# teensyPCB.net
KiCad netlist of a schematic drawn in EAGLE
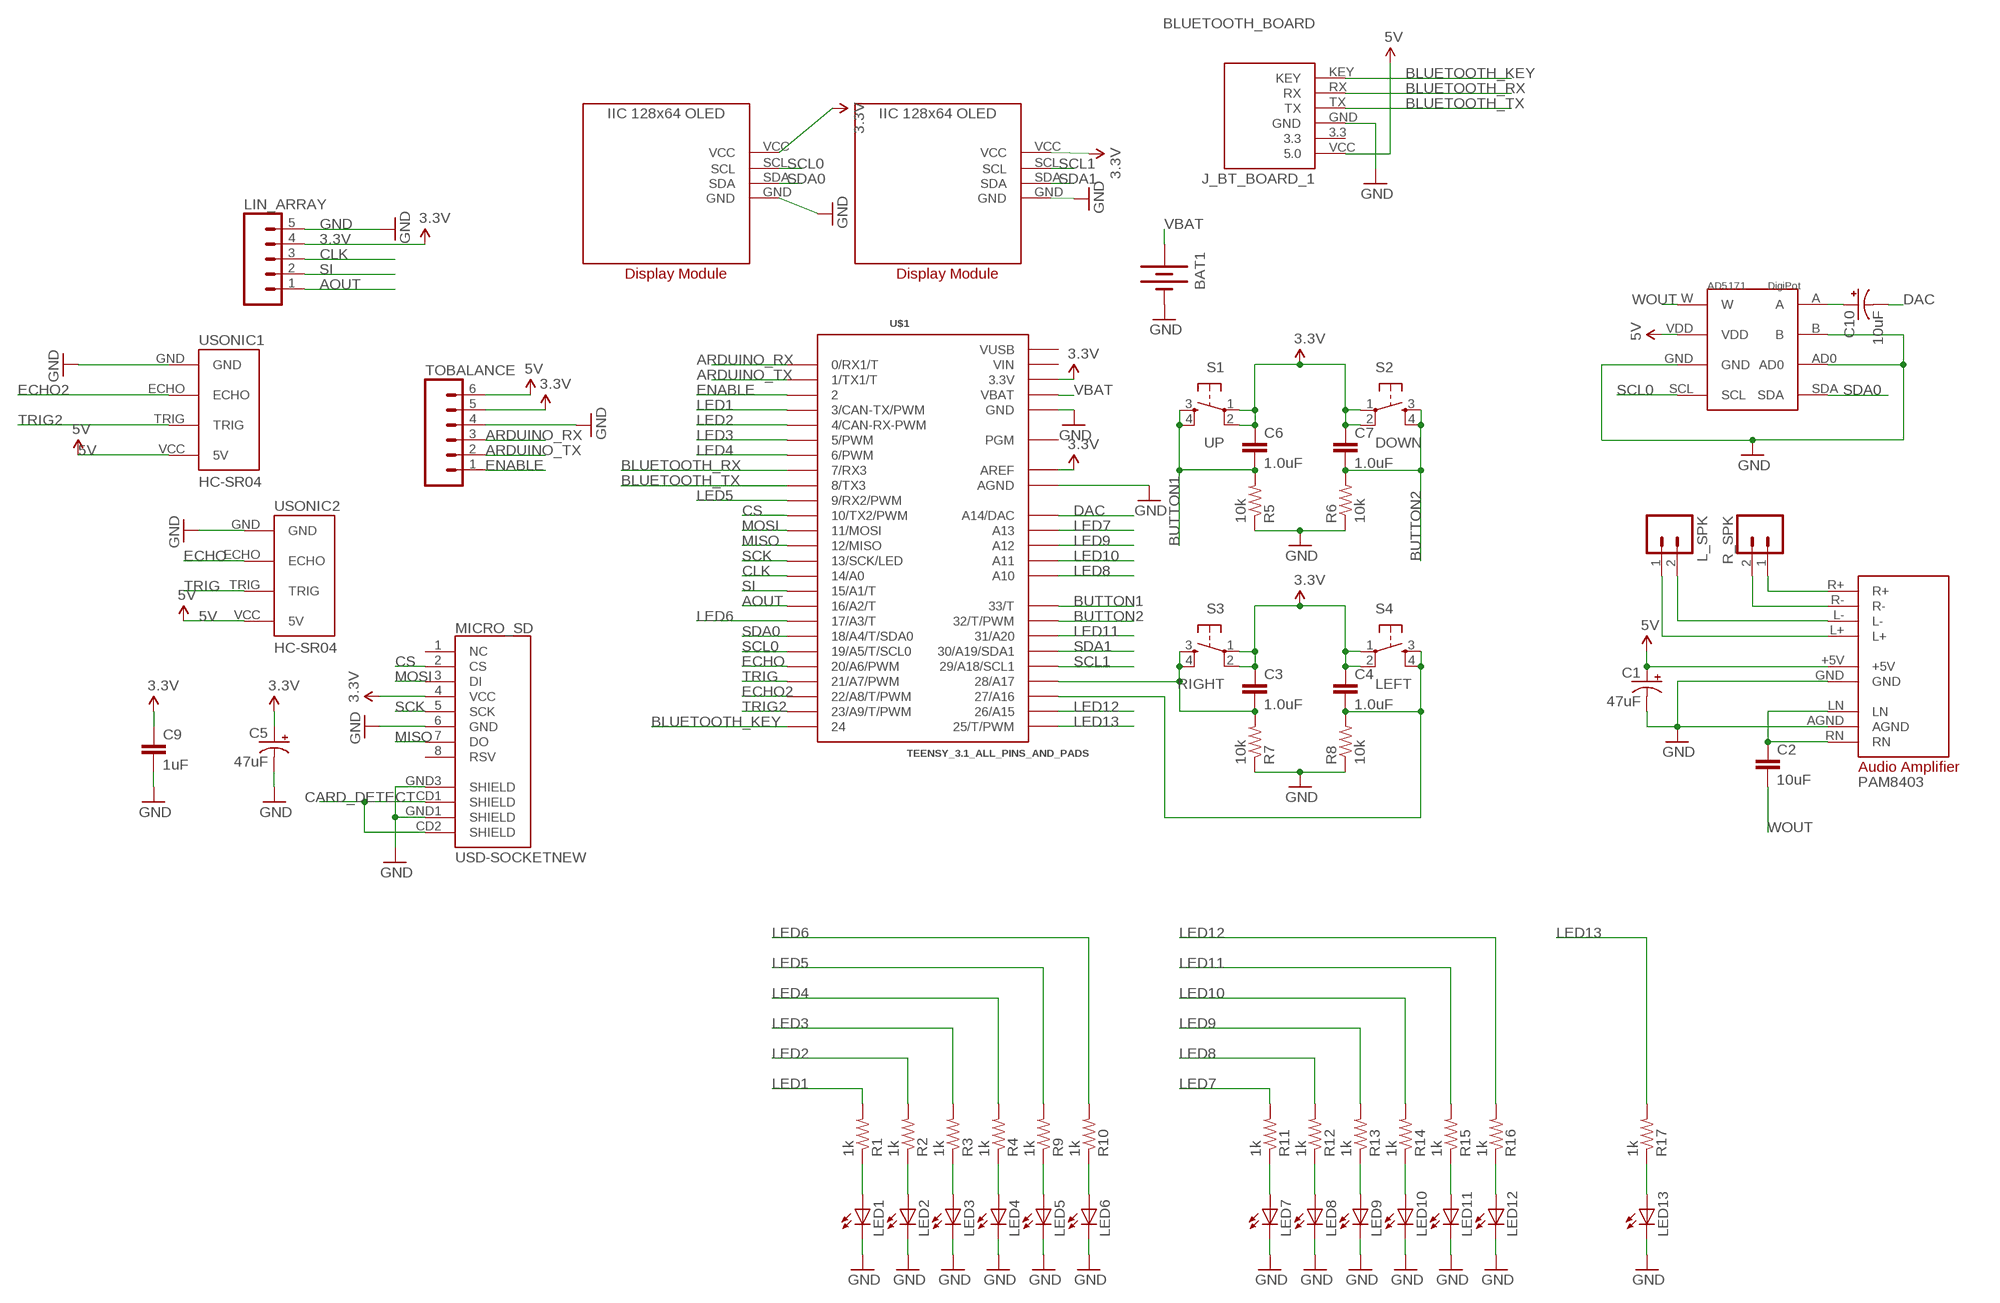
[diagram p0: schematic, sheet 1]

(export (version "E")
  (design (tool "Eeschema 10.0.6"))
  (components
    (comp (ref "BAT1")
      (value "BATTERY20PTH")
      (footprint "eagle-import:BATTCOM_20MM_PTH")
      (libsource (lib "eagle-import") (part "BATTERY20PTH"))
    )
    (comp (ref "C1")
      (value "47uF")
      (footprint "eagle-import:EIA3528")
      (libsource (lib "eagle-import") (part "CAP_POL3528"))
    )
    (comp (ref "C2")
      (value "10uF")
      (footprint "eagle-import:0805")
      (libsource (lib "eagle-import") (part "1.0UF-25V-+80/-20(0805)"))
    )
    (comp (ref "C3")
      (value "1.0uF")
      (footprint "eagle-import:0805")
      (libsource (lib "eagle-import") (part "1.0UF-25V-+80/-20(0805)"))
    )
    (comp (ref "C4")
      (value "1.0uF")
      (footprint "eagle-import:0805")
      (libsource (lib "eagle-import") (part "1.0UF-25V-+80/-20(0805)"))
    )
    (comp (ref "C5")
      (value "47uF")
      (footprint "eagle-import:EIA3528")
      (libsource (lib "eagle-import") (part "CAP_POL3528"))
    )
    (comp (ref "C6")
      (value "1.0uF")
      (footprint "eagle-import:0805")
      (libsource (lib "eagle-import") (part "1.0UF-25V-+80/-20(0805)"))
    )
    (comp (ref "C7")
      (value "1.0uF")
      (footprint "eagle-import:0805")
      (libsource (lib "eagle-import") (part "1.0UF-25V-+80/-20(0805)"))
    )
    (comp (ref "C9")
      (value "1uF")
      (footprint "eagle-import:0805")
      (libsource (lib "eagle-import") (part "1.0UF-25V-+80/-20(0805)"))
    )
    (comp (ref "C10")
      (value "10uF")
      (footprint "eagle-import:EIA3528")
      (libsource (lib "eagle-import") (part "CAP_POL3528"))
    )
    (comp (ref "J_BT_BOARD_1")
      (value "BLUETOOTH_BOARD")
      (footprint "eagle-import:BT_BOARD_FOOTPRINT")
      (libsource (lib "eagle-import") (part "BLUETOOTH_BOARD"))
    )
    (comp (ref "LED1")
      (value "LEDCHIP-LED0805")
      (footprint "eagle-import:CHIP-LED0805")
      (libsource (lib "eagle-import") (part "LEDCHIP-LED0805"))
    )
    (comp (ref "LED2")
      (value "LEDCHIP-LED0805")
      (footprint "eagle-import:CHIP-LED0805")
      (libsource (lib "eagle-import") (part "LEDCHIP-LED0805"))
    )
    (comp (ref "LED3")
      (value "LEDCHIP-LED0805")
      (footprint "eagle-import:CHIP-LED0805")
      (libsource (lib "eagle-import") (part "LEDCHIP-LED0805"))
    )
    (comp (ref "LED4")
      (value "LEDCHIP-LED0805")
      (footprint "eagle-import:CHIP-LED0805")
      (libsource (lib "eagle-import") (part "LEDCHIP-LED0805"))
    )
    (comp (ref "LED5")
      (value "LEDCHIP-LED0805")
      (footprint "eagle-import:CHIP-LED0805")
      (libsource (lib "eagle-import") (part "LEDCHIP-LED0805"))
    )
    (comp (ref "LED6")
      (value "LEDCHIP-LED0805")
      (footprint "eagle-import:CHIP-LED0805")
      (libsource (lib "eagle-import") (part "LEDCHIP-LED0805"))
    )
    (comp (ref "LED7")
      (value "LEDCHIP-LED0805")
      (footprint "eagle-import:CHIP-LED0805")
      (libsource (lib "eagle-import") (part "LEDCHIP-LED0805"))
    )
    (comp (ref "LED8")
      (value "LEDCHIP-LED0805")
      (footprint "eagle-import:CHIP-LED0805")
      (libsource (lib "eagle-import") (part "LEDCHIP-LED0805"))
    )
    (comp (ref "LED9")
      (value "LEDCHIP-LED0805")
      (footprint "eagle-import:CHIP-LED0805")
      (libsource (lib "eagle-import") (part "LEDCHIP-LED0805"))
    )
    (comp (ref "LED10")
      (value "LEDCHIP-LED0805")
      (footprint "eagle-import:CHIP-LED0805")
      (libsource (lib "eagle-import") (part "LEDCHIP-LED0805"))
    )
    (comp (ref "LED11")
      (value "LEDCHIP-LED0805")
      (footprint "eagle-import:CHIP-LED0805")
      (libsource (lib "eagle-import") (part "LEDCHIP-LED0805"))
    )
    (comp (ref "LED12")
      (value "LEDCHIP-LED0805")
      (footprint "eagle-import:CHIP-LED0805")
      (libsource (lib "eagle-import") (part "LEDCHIP-LED0805"))
    )
    (comp (ref "LED13")
      (value "LEDCHIP-LED0805")
      (footprint "eagle-import:CHIP-LED0805")
      (libsource (lib "eagle-import") (part "LEDCHIP-LED0805"))
    )
    (comp (ref "LIN_ARRAY")
      (value "M05LOCK")
      (footprint "eagle-import:1X05_LOCK")
      (libsource (lib "eagle-import") (part "M05LOCK"))
    )
    (comp (ref "L_SPK")
      (value "M02PTH")
      (footprint "eagle-import:1X02")
      (libsource (lib "eagle-import") (part "M02PTH"))
    )
    (comp (ref "MICRO_SD")
      (value "USD-SOCKETNEW")
      (footprint "eagle-import:MICRO-SD-SOCKET-PP")
      (libsource (lib "eagle-import") (part "USD-SOCKETNEW"))
    )
    (comp (ref "R1")
      (value "1k")
      (footprint "eagle-import:0805")
      (libsource (lib "eagle-import") (part "RESISTOR0805-RES"))
    )
    (comp (ref "R2")
      (value "1k")
      (footprint "eagle-import:0805")
      (libsource (lib "eagle-import") (part "RESISTOR0805-RES"))
    )
    (comp (ref "R3")
      (value "1k")
      (footprint "eagle-import:0805")
      (libsource (lib "eagle-import") (part "RESISTOR0805-RES"))
    )
    (comp (ref "R4")
      (value "1k")
      (footprint "eagle-import:0805")
      (libsource (lib "eagle-import") (part "RESISTOR0805-RES"))
    )
    (comp (ref "R5")
      (value "10k")
      (footprint "eagle-import:0805")
      (libsource (lib "eagle-import") (part "RESISTOR0805-RES"))
    )
    (comp (ref "R6")
      (value "10k")
      (footprint "eagle-import:0805")
      (libsource (lib "eagle-import") (part "RESISTOR0805-RES"))
    )
    (comp (ref "R7")
      (value "10k")
      (footprint "eagle-import:0805")
      (libsource (lib "eagle-import") (part "RESISTOR0805-RES"))
    )
    (comp (ref "R8")
      (value "10k")
      (footprint "eagle-import:0805")
      (libsource (lib "eagle-import") (part "RESISTOR0805-RES"))
    )
    (comp (ref "R9")
      (value "1k")
      (footprint "eagle-import:0805")
      (libsource (lib "eagle-import") (part "RESISTOR0805-RES"))
    )
    (comp (ref "R10")
      (value "1k")
      (footprint "eagle-import:0805")
      (libsource (lib "eagle-import") (part "RESISTOR0805-RES"))
    )
    (comp (ref "R11")
      (value "1k")
      (footprint "eagle-import:0805")
      (libsource (lib "eagle-import") (part "RESISTOR0805-RES"))
    )
    (comp (ref "R12")
      (value "1k")
      (footprint "eagle-import:0805")
      (libsource (lib "eagle-import") (part "RESISTOR0805-RES"))
    )
    (comp (ref "R13")
      (value "1k")
      (footprint "eagle-import:0805")
      (libsource (lib "eagle-import") (part "RESISTOR0805-RES"))
    )
    (comp (ref "R14")
      (value "1k")
      (footprint "eagle-import:0805")
      (libsource (lib "eagle-import") (part "RESISTOR0805-RES"))
    )
    (comp (ref "R15")
      (value "1k")
      (footprint "eagle-import:0805")
      (libsource (lib "eagle-import") (part "RESISTOR0805-RES"))
    )
    (comp (ref "R16")
      (value "1k")
      (footprint "eagle-import:0805")
      (libsource (lib "eagle-import") (part "RESISTOR0805-RES"))
    )
    (comp (ref "R17")
      (value "1k")
      (footprint "eagle-import:0805")
      (libsource (lib "eagle-import") (part "RESISTOR0805-RES"))
    )
    (comp (ref "R_SPK")
      (value "M02PTH")
      (footprint "eagle-import:1X02")
      (libsource (lib "eagle-import") (part "M02PTH"))
    )
    (comp (ref "S1")
      (value "UP")
      (footprint "eagle-import:TACTILE-SWITCH-SMD")
      (libsource (lib "eagle-import") (part "TAC_SWITCHSMD"))
    )
    (comp (ref "S2")
      (value "DOWN")
      (footprint "eagle-import:TACTILE-SWITCH-SMD")
      (libsource (lib "eagle-import") (part "TAC_SWITCHSMD"))
    )
    (comp (ref "S3")
      (value "RIGHT")
      (footprint "eagle-import:TACTILE-SWITCH-SMD")
      (libsource (lib "eagle-import") (part "TAC_SWITCHSMD"))
    )
    (comp (ref "S4")
      (value "LEFT")
      (footprint "eagle-import:TACTILE-SWITCH-SMD")
      (libsource (lib "eagle-import") (part "TAC_SWITCHSMD"))
    )
    (comp (ref "TOBALANCE")
      (value "M06POLAR_LOCK")
      (footprint "eagle-import:MOLEX-1X6_LOCK")
      (libsource (lib "eagle-import") (part "M06POLAR_LOCK"))
    )
    (comp (ref "U$1")
      (value "TEENSY_3.1_ALL_PINS_AND_PADS")
      (footprint "eagle-import:TEENSY3_ALL_PINS_&_PADS")
      (libsource (lib "eagle-import") (part "TEENSY_3.1_ALL_PINS_AND_PADS"))
    )
    (comp (ref "U$2")
      (value "IIC128X64OLED")
      (footprint "eagle-import:IIC128X64OLED")
      (libsource (lib "eagle-import") (part "IIC128X64OLED"))
    )
    (comp (ref "U$3")
      (value "IIC128X64OLED")
      (footprint "eagle-import:IIC128X64OLED")
      (libsource (lib "eagle-import") (part "IIC128X64OLED"))
    )
    (comp (ref "U$4")
      (value "AUDIOAMPEBAY_VERSION")
      (footprint "eagle-import:AUDIOAMP")
      (libsource (lib "eagle-import") (part "AUDIOAMPEBAY_VERSION"))
    )
    (comp (ref "U$5")
      (value "DIGIPOT")
      (footprint "eagle-import:SOT23-8L")
      (libsource (lib "eagle-import") (part "DIGIPOT"))
    )
    (comp (ref "USONIC1")
      (value "HC-SR04")
      (footprint "eagle-import:HC-SR04_FOOTPRINT")
      (libsource (lib "eagle-import") (part "HC-SR04"))
    )
    (comp (ref "USONIC2")
      (value "HC-SR04")
      (footprint "eagle-import:HC-SR04_FOOTPRINT")
      (libsource (lib "eagle-import") (part "HC-SR04"))
    )
  )
  (nets
    (net (code "1") (name "/AOUT") (class "Default")
      (node (ref "LIN_ARRAY") (pin "1") (pinfunction "1_1") (pintype "passive"))
      (node (ref "U$1") (pin "16/A2") (pinfunction "16/A2/T_16/A2") (pintype "bidirectional"))
    )
    (net (code "2") (name "/ARDUINO_RX") (class "Default")
      (node (ref "TOBALANCE") (pin "3") (pinfunction "3_3") (pintype "passive"))
      (node (ref "U$1") (pin "0") (pinfunction "0/RX1/T_0") (pintype "bidirectional"))
    )
    (net (code "3") (name "/ARDUINO_TX") (class "Default")
      (node (ref "TOBALANCE") (pin "2") (pinfunction "2_2") (pintype "passive"))
      (node (ref "U$1") (pin "1") (pinfunction "1/TX1/T_1") (pintype "bidirectional"))
    )
    (net (code "4") (name "/BLUETOOTH_KEY") (class "Default")
      (node (ref "J_BT_BOARD_1") (pin "KEY") (pinfunction "KEY_KEY") (pintype "bidirectional"))
      (node (ref "U$1") (pin "24") (pinfunction "24_24") (pintype "bidirectional"))
    )
    (net (code "5") (name "/BLUETOOTH_RX") (class "Default")
      (node (ref "J_BT_BOARD_1") (pin "RX") (pinfunction "RX_RX") (pintype "bidirectional"))
      (node (ref "U$1") (pin "7") (pinfunction "7/RX3_7") (pintype "bidirectional"))
    )
    (net (code "6") (name "/BLUETOOTH_TX") (class "Default")
      (node (ref "J_BT_BOARD_1") (pin "TX") (pinfunction "TX_TX") (pintype "bidirectional"))
      (node (ref "U$1") (pin "8") (pinfunction "8/TX3_8") (pintype "bidirectional"))
    )
    (net (code "7") (name "/BUTTON1") (class "Default")
      (node (ref "C6") (pin "2") (pinfunction "2_2") (pintype "passive"))
      (node (ref "R5") (pin "2") (pinfunction "2_2") (pintype "passive"))
      (node (ref "S1") (pin "3") (pinfunction "3_3") (pintype "passive"))
      (node (ref "S1") (pin "4") (pinfunction "4_4") (pintype "passive"))
      (node (ref "U$1") (pin "33") (pinfunction "33/T_33") (pintype "bidirectional"))
    )
    (net (code "8") (name "/BUTTON2") (class "Default")
      (node (ref "C7") (pin "2") (pinfunction "2_2") (pintype "passive"))
      (node (ref "R6") (pin "2") (pinfunction "2_2") (pintype "passive"))
      (node (ref "S2") (pin "3") (pinfunction "3_3") (pintype "passive"))
      (node (ref "S2") (pin "4") (pinfunction "4_4") (pintype "passive"))
      (node (ref "U$1") (pin "32") (pinfunction "32/T/PWM_32") (pintype "bidirectional"))
    )
    (net (code "9") (name "/CARD_DETECT") (class "Default")
      (node (ref "MICRO_SD") (pin "CD1") (pinfunction "SHIELD_CD1") (pintype "bidirectional"))
      (node (ref "MICRO_SD") (pin "CD2") (pinfunction "SHIELD_CD2") (pintype "bidirectional"))
    )
    (net (code "10") (name "/CLK") (class "Default")
      (node (ref "LIN_ARRAY") (pin "3") (pinfunction "3_3") (pintype "passive"))
      (node (ref "U$1") (pin "14/A0") (pinfunction "14/A0_14/A0") (pintype "bidirectional"))
    )
    (net (code "11") (name "/CS") (class "Default")
      (node (ref "MICRO_SD") (pin "2") (pinfunction "CS_2") (pintype "bidirectional"))
      (node (ref "U$1") (pin "10") (pinfunction "10/TX2/PWM_10") (pintype "bidirectional"))
    )
    (net (code "12") (name "/DAC") (class "Default")
      (node (ref "C10") (pin "C") (pinfunction "-_C") (pintype "passive"))
      (node (ref "U$1") (pin "RESET/DAC") (pinfunction "A14/DAC_RESET/DAC") (pintype "bidirectional"))
    )
    (net (code "13") (name "/ECHO") (class "Default")
      (node (ref "U$1") (pin "20/A6") (pinfunction "20/A6/PWM_20/A6") (pintype "bidirectional"))
      (node (ref "USONIC2") (pin "ECHO") (pinfunction "ECHO_ECHO") (pintype "bidirectional"))
    )
    (net (code "14") (name "/ECHO2") (class "Default")
      (node (ref "U$1") (pin "22/A8") (pinfunction "22/A8/T/PWM_22/A8") (pintype "bidirectional"))
      (node (ref "USONIC1") (pin "ECHO") (pinfunction "ECHO_ECHO") (pintype "bidirectional"))
    )
    (net (code "15") (name "/ENABLE") (class "Default")
      (node (ref "TOBALANCE") (pin "1") (pinfunction "1_1") (pintype "passive"))
      (node (ref "U$1") (pin "2") (pinfunction "2_2") (pintype "bidirectional"))
    )
    (net (code "16") (name "/LED1") (class "Default")
      (node (ref "R1") (pin "2") (pinfunction "2_2") (pintype "passive"))
      (node (ref "U$1") (pin "3") (pinfunction "3/CAN-TX/PWM_3") (pintype "bidirectional"))
    )
    (net (code "17") (name "/LED2") (class "Default")
      (node (ref "R2") (pin "2") (pinfunction "2_2") (pintype "passive"))
      (node (ref "U$1") (pin "4") (pinfunction "4/CAN-RX-PWM_4") (pintype "bidirectional"))
    )
    (net (code "18") (name "/LED3") (class "Default")
      (node (ref "R3") (pin "2") (pinfunction "2_2") (pintype "passive"))
      (node (ref "U$1") (pin "5") (pinfunction "5/PWM_5") (pintype "bidirectional"))
    )
    (net (code "19") (name "/LED4") (class "Default")
      (node (ref "R4") (pin "2") (pinfunction "2_2") (pintype "passive"))
      (node (ref "U$1") (pin "6") (pinfunction "6/PWM_6") (pintype "bidirectional"))
    )
    (net (code "20") (name "/LED5") (class "Default")
      (node (ref "R9") (pin "2") (pinfunction "2_2") (pintype "passive"))
      (node (ref "U$1") (pin "9") (pinfunction "9/RX2/PWM_9") (pintype "bidirectional"))
    )
    (net (code "21") (name "/LED6") (class "Default")
      (node (ref "R10") (pin "2") (pinfunction "2_2") (pintype "passive"))
      (node (ref "U$1") (pin "17/A3") (pinfunction "17/A3/T_17/A3") (pintype "bidirectional"))
    )
    (net (code "22") (name "/LED7") (class "Default")
      (node (ref "R11") (pin "2") (pinfunction "2_2") (pintype "passive"))
      (node (ref "U$1") (pin "A13") (pinfunction "A13_A13") (pintype "bidirectional"))
    )
    (net (code "23") (name "/LED8") (class "Default")
      (node (ref "R12") (pin "2") (pinfunction "2_2") (pintype "passive"))
      (node (ref "U$1") (pin "A10") (pinfunction "A10_A10") (pintype "bidirectional"))
    )
    (net (code "24") (name "/LED9") (class "Default")
      (node (ref "R13") (pin "2") (pinfunction "2_2") (pintype "passive"))
      (node (ref "U$1") (pin "A12") (pinfunction "A12_A12") (pintype "bidirectional"))
    )
    (net (code "25") (name "/LED10") (class "Default")
      (node (ref "R14") (pin "2") (pinfunction "2_2") (pintype "passive"))
      (node (ref "U$1") (pin "A11") (pinfunction "A11_A11") (pintype "bidirectional"))
    )
    (net (code "26") (name "/LED11") (class "Default")
      (node (ref "R15") (pin "2") (pinfunction "2_2") (pintype "passive"))
      (node (ref "U$1") (pin "31") (pinfunction "31/A20_31") (pintype "bidirectional"))
    )
    (net (code "27") (name "/LED12") (class "Default")
      (node (ref "R16") (pin "2") (pinfunction "2_2") (pintype "passive"))
      (node (ref "U$1") (pin "26") (pinfunction "26/A15_26") (pintype "bidirectional"))
    )
    (net (code "28") (name "/LED13") (class "Default")
      (node (ref "R17") (pin "2") (pinfunction "2_2") (pintype "passive"))
      (node (ref "U$1") (pin "25") (pinfunction "25/T/PWM_25") (pintype "bidirectional"))
    )
    (net (code "29") (name "/MISO") (class "Default")
      (node (ref "MICRO_SD") (pin "7") (pinfunction "DO_7") (pintype "bidirectional"))
      (node (ref "U$1") (pin "12") (pinfunction "12/MISO_12") (pintype "bidirectional"))
    )
    (net (code "30") (name "/MOSI") (class "Default")
      (node (ref "MICRO_SD") (pin "3") (pinfunction "DI_3") (pintype "bidirectional"))
      (node (ref "U$1") (pin "11") (pinfunction "11/MOSI_11") (pintype "bidirectional"))
    )
    (net (code "31") (name "/SCK") (class "Default")
      (node (ref "MICRO_SD") (pin "5") (pinfunction "SCK_5") (pintype "bidirectional"))
      (node (ref "U$1") (pin "13") (pinfunction "13/SCK/LED_13") (pintype "bidirectional"))
    )
    (net (code "32") (name "/SCL0") (class "Default")
      (node (ref "U$1") (pin "19/A5") (pinfunction "19/A5/T/SCL0_19/A5") (pintype "bidirectional"))
      (node (ref "U$2") (pin "SCL") (pinfunction "SCL_SCL") (pintype "bidirectional"))
      (node (ref "U$5") (pin "SCL") (pinfunction "SCL_SCL") (pintype "bidirectional"))
    )
    (net (code "33") (name "/SCL1") (class "Default")
      (node (ref "U$1") (pin "29") (pinfunction "29/A18/SCL1_29") (pintype "bidirectional"))
      (node (ref "U$3") (pin "SCL") (pinfunction "SCL_SCL") (pintype "bidirectional"))
    )
    (net (code "34") (name "/SDA0") (class "Default")
      (node (ref "U$1") (pin "18/A4") (pinfunction "18/A4/T/SDA0_18/A4") (pintype "bidirectional"))
      (node (ref "U$2") (pin "SDA") (pinfunction "SDA_SDA") (pintype "bidirectional"))
      (node (ref "U$5") (pin "SDA") (pinfunction "SDA_SDA") (pintype "bidirectional"))
    )
    (net (code "35") (name "/SDA1") (class "Default")
      (node (ref "U$1") (pin "30") (pinfunction "30/A19/SDA1_30") (pintype "bidirectional"))
      (node (ref "U$3") (pin "SDA") (pinfunction "SDA_SDA") (pintype "bidirectional"))
    )
    (net (code "36") (name "/SI") (class "Default")
      (node (ref "LIN_ARRAY") (pin "2") (pinfunction "2_2") (pintype "passive"))
      (node (ref "U$1") (pin "15/A1") (pinfunction "15/A1/T_15/A1") (pintype "bidirectional"))
    )
    (net (code "37") (name "/TRIG") (class "Default")
      (node (ref "U$1") (pin "21/A7") (pinfunction "21/A7/PWM_21/A7") (pintype "bidirectional"))
      (node (ref "USONIC2") (pin "TRIG") (pinfunction "TRIG_TRIG") (pintype "bidirectional"))
    )
    (net (code "38") (name "/TRIG2") (class "Default")
      (node (ref "U$1") (pin "23/A9") (pinfunction "23/A9/T/PWM_23/A9") (pintype "bidirectional"))
      (node (ref "USONIC1") (pin "TRIG") (pinfunction "TRIG_TRIG") (pintype "bidirectional"))
    )
    (net (code "39") (name "/VBAT") (class "Default")
      (node (ref "BAT1") (pin "1") (pinfunction "+_1") (pintype "power_in"))
      (node (ref "U$1") (pin "VBAT") (pinfunction "VBAT_VBAT") (pintype "power_in"))
    )
    (net (code "40") (name "/VIN") (class "Default")
      (node (ref "U$1") (pin "VIN") (pinfunction "VIN_VIN") (pintype "power_in"))
    )
    (net (code "41") (name "/VUSB") (class "Default")
      (node (ref "U$1") (pin "VUSB") (pinfunction "VUSB_VUSB") (pintype "power_in"))
    )
    (net (code "42") (name "/WOUT") (class "Default")
      (node (ref "C2") (pin "2") (pinfunction "2_2") (pintype "passive"))
      (node (ref "U$5") (pin "W") (pinfunction "W_W") (pintype "bidirectional"))
    )
    (net (code "43") (name "3.3V") (class "Default")
      (node (ref "C3") (pin "1") (pinfunction "1_1") (pintype "passive"))
      (node (ref "C4") (pin "1") (pinfunction "1_1") (pintype "passive"))
      (node (ref "C5") (pin "A") (pinfunction "+_A") (pintype "passive"))
      (node (ref "C6") (pin "1") (pinfunction "1_1") (pintype "passive"))
      (node (ref "C7") (pin "1") (pinfunction "1_1") (pintype "passive"))
      (node (ref "C9") (pin "1") (pinfunction "1_1") (pintype "passive"))
      (node (ref "LIN_ARRAY") (pin "4") (pinfunction "4_4") (pintype "passive"))
      (node (ref "MICRO_SD") (pin "4") (pinfunction "VCC_4") (pintype "bidirectional"))
      (node (ref "S1") (pin "1") (pinfunction "1_1") (pintype "passive"))
      (node (ref "S1") (pin "2") (pinfunction "2_2") (pintype "passive"))
      (node (ref "S2") (pin "1") (pinfunction "1_1") (pintype "passive"))
      (node (ref "S2") (pin "2") (pinfunction "2_2") (pintype "passive"))
      (node (ref "S3") (pin "1") (pinfunction "1_1") (pintype "passive"))
      (node (ref "S3") (pin "2") (pinfunction "2_2") (pintype "passive"))
      (node (ref "S4") (pin "1") (pinfunction "1_1") (pintype "passive"))
      (node (ref "S4") (pin "2") (pinfunction "2_2") (pintype "passive"))
      (node (ref "TOBALANCE") (pin "5") (pinfunction "5_5") (pintype "passive"))
      (node (ref "U$1") (pin "3.3V") (pinfunction "3.3V_3.3V") (pintype "power_in"))
      (node (ref "U$1") (pin "3.3V1") (pinfunction "3.3V_3.3V1") (pintype "power_in"))
      (node (ref "U$1") (pin "3.3V2") (pinfunction "3.3V_3.3V2") (pintype "power_in"))
      (node (ref "U$1") (pin "AREF") (pinfunction "AREF_AREF") (pintype "power_in"))
      (node (ref "U$2") (pin "VCC") (pinfunction "VCC_VCC") (pintype "bidirectional"))
      (node (ref "U$3") (pin "VCC") (pinfunction "VCC_VCC") (pintype "bidirectional"))
    )
    (net (code "44") (name "5V") (class "Default")
      (node (ref "C1") (pin "A") (pinfunction "+_A") (pintype "passive"))
      (node (ref "J_BT_BOARD_1") (pin "VCC") (pinfunction "5.0_VCC") (pintype "bidirectional"))
      (node (ref "TOBALANCE") (pin "6") (pinfunction "6_6") (pintype "passive"))
      (node (ref "U$4") (pin "+5V") (pinfunction "+5V_+5V") (pintype "power_in"))
      (node (ref "U$5") (pin "VDD") (pinfunction "VDD_VDD") (pintype "bidirectional"))
      (node (ref "USONIC1") (pin "VCC") (pinfunction "5V_VCC") (pintype "bidirectional"))
      (node (ref "USONIC2") (pin "VCC") (pinfunction "5V_VCC") (pintype "bidirectional"))
    )
    (net (code "45") (name "GND") (class "Default")
      (node (ref "BAT1") (pin "2") (pinfunction "-_2") (pintype "power_in"))
      (node (ref "C1") (pin "C") (pinfunction "-_C") (pintype "passive"))
      (node (ref "C5") (pin "C") (pinfunction "-_C") (pintype "passive"))
      (node (ref "C9") (pin "2") (pinfunction "2_2") (pintype "passive"))
      (node (ref "J_BT_BOARD_1") (pin "GND") (pinfunction "GND_GND") (pintype "bidirectional"))
      (node (ref "LED1") (pin "C") (pinfunction "C_C") (pintype "passive"))
      (node (ref "LED10") (pin "C") (pinfunction "C_C") (pintype "passive"))
      (node (ref "LED11") (pin "C") (pinfunction "C_C") (pintype "passive"))
      (node (ref "LED12") (pin "C") (pinfunction "C_C") (pintype "passive"))
      (node (ref "LED13") (pin "C") (pinfunction "C_C") (pintype "passive"))
      (node (ref "LED2") (pin "C") (pinfunction "C_C") (pintype "passive"))
      (node (ref "LED3") (pin "C") (pinfunction "C_C") (pintype "passive"))
      (node (ref "LED4") (pin "C") (pinfunction "C_C") (pintype "passive"))
      (node (ref "LED5") (pin "C") (pinfunction "C_C") (pintype "passive"))
      (node (ref "LED6") (pin "C") (pinfunction "C_C") (pintype "passive"))
      (node (ref "LED7") (pin "C") (pinfunction "C_C") (pintype "passive"))
      (node (ref "LED8") (pin "C") (pinfunction "C_C") (pintype "passive"))
      (node (ref "LED9") (pin "C") (pinfunction "C_C") (pintype "passive"))
      (node (ref "LIN_ARRAY") (pin "5") (pinfunction "5_5") (pintype "passive"))
      (node (ref "MICRO_SD") (pin "6") (pinfunction "GND_6") (pintype "bidirectional"))
      (node (ref "MICRO_SD") (pin "GND1") (pinfunction "SHIELD_GND1") (pintype "bidirectional"))
      (node (ref "MICRO_SD") (pin "GND3") (pinfunction "SHIELD_GND3") (pintype "bidirectional"))
      (node (ref "R5") (pin "1") (pinfunction "1_1") (pintype "passive"))
      (node (ref "R6") (pin "1") (pinfunction "1_1") (pintype "passive"))
      (node (ref "R7") (pin "1") (pinfunction "1_1") (pintype "passive"))
      (node (ref "R8") (pin "1") (pinfunction "1_1") (pintype "passive"))
      (node (ref "TOBALANCE") (pin "4") (pinfunction "4_4") (pintype "passive"))
      (node (ref "U$1") (pin "AGND") (pinfunction "AGND_AGND") (pintype "power_in"))
      (node (ref "U$1") (pin "GND") (pinfunction "GND_GND") (pintype "power_in"))
      (node (ref "U$1") (pin "GND1") (pinfunction "GND_GND1") (pintype "power_in"))
      (node (ref "U$1") (pin "GND2") (pinfunction "GND_GND2") (pintype "power_in"))
      (node (ref "U$2") (pin "GND") (pinfunction "GND_GND") (pintype "bidirectional"))
      (node (ref "U$3") (pin "GND") (pinfunction "GND_GND") (pintype "bidirectional"))
      (node (ref "U$4") (pin "AGND") (pinfunction "AGND_AGND") (pintype "bidirectional"))
      (node (ref "U$4") (pin "GND") (pinfunction "GND_GND") (pintype "power_in"))
      (node (ref "U$5") (pin "AD0") (pinfunction "AD0_AD0") (pintype "bidirectional"))
      (node (ref "U$5") (pin "B") (pinfunction "B_B") (pintype "bidirectional"))
      (node (ref "U$5") (pin "GND") (pinfunction "GND_GND") (pintype "bidirectional"))
      (node (ref "USONIC1") (pin "GND") (pinfunction "GND_GND") (pintype "bidirectional"))
      (node (ref "USONIC2") (pin "GND") (pinfunction "GND_GND") (pintype "bidirectional"))
    )
    (net (code "46") (name "Net-(C2-Pad1)") (class "Default")
      (node (ref "C2") (pin "1") (pinfunction "1_1") (pintype "passive"))
      (node (ref "U$4") (pin "LN") (pinfunction "LN_LN") (pintype "bidirectional"))
      (node (ref "U$4") (pin "RN") (pinfunction "RN_RN") (pintype "bidirectional"))
    )
    (net (code "47") (name "Net-(C10-+)") (class "Default")
      (node (ref "C10") (pin "A") (pinfunction "+_A") (pintype "passive"))
      (node (ref "U$5") (pin "A") (pinfunction "A_A") (pintype "bidirectional"))
    )
    (net (code "48") (name "Net-(LED1-PadA)") (class "Default")
      (node (ref "LED1") (pin "A") (pinfunction "A_A") (pintype "passive"))
      (node (ref "R1") (pin "1") (pinfunction "1_1") (pintype "passive"))
    )
    (net (code "49") (name "Net-(LED2-PadA)") (class "Default")
      (node (ref "LED2") (pin "A") (pinfunction "A_A") (pintype "passive"))
      (node (ref "R2") (pin "1") (pinfunction "1_1") (pintype "passive"))
    )
    (net (code "50") (name "Net-(LED3-PadA)") (class "Default")
      (node (ref "LED3") (pin "A") (pinfunction "A_A") (pintype "passive"))
      (node (ref "R3") (pin "1") (pinfunction "1_1") (pintype "passive"))
    )
    (net (code "51") (name "Net-(LED4-PadA)") (class "Default")
      (node (ref "LED4") (pin "A") (pinfunction "A_A") (pintype "passive"))
      (node (ref "R4") (pin "1") (pinfunction "1_1") (pintype "passive"))
    )
    (net (code "52") (name "Net-(LED5-PadA)") (class "Default")
      (node (ref "LED5") (pin "A") (pinfunction "A_A") (pintype "passive"))
      (node (ref "R9") (pin "1") (pinfunction "1_1") (pintype "passive"))
    )
    (net (code "53") (name "Net-(LED6-PadA)") (class "Default")
      (node (ref "LED6") (pin "A") (pinfunction "A_A") (pintype "passive"))
      (node (ref "R10") (pin "1") (pinfunction "1_1") (pintype "passive"))
    )
    (net (code "54") (name "Net-(LED7-PadA)") (class "Default")
      (node (ref "LED7") (pin "A") (pinfunction "A_A") (pintype "passive"))
      (node (ref "R11") (pin "1") (pinfunction "1_1") (pintype "passive"))
    )
    (net (code "55") (name "Net-(LED8-PadA)") (class "Default")
      (node (ref "LED8") (pin "A") (pinfunction "A_A") (pintype "passive"))
      (node (ref "R12") (pin "1") (pinfunction "1_1") (pintype "passive"))
    )
    (net (code "56") (name "Net-(LED9-PadA)") (class "Default")
      (node (ref "LED9") (pin "A") (pinfunction "A_A") (pintype "passive"))
      (node (ref "R13") (pin "1") (pinfunction "1_1") (pintype "passive"))
    )
    (net (code "57") (name "Net-(LED10-PadA)") (class "Default")
      (node (ref "LED10") (pin "A") (pinfunction "A_A") (pintype "passive"))
      (node (ref "R14") (pin "1") (pinfunction "1_1") (pintype "passive"))
    )
    (net (code "58") (name "Net-(LED11-PadA)") (class "Default")
      (node (ref "LED11") (pin "A") (pinfunction "A_A") (pintype "passive"))
      (node (ref "R15") (pin "1") (pinfunction "1_1") (pintype "passive"))
    )
    (net (code "59") (name "Net-(LED12-PadA)") (class "Default")
      (node (ref "LED12") (pin "A") (pinfunction "A_A") (pintype "passive"))
      (node (ref "R16") (pin "1") (pinfunction "1_1") (pintype "passive"))
    )
    (net (code "60") (name "Net-(LED13-PadA)") (class "Default")
      (node (ref "LED13") (pin "A") (pinfunction "A_A") (pintype "passive"))
      (node (ref "R17") (pin "1") (pinfunction "1_1") (pintype "passive"))
    )
    (net (code "61") (name "Net-(L_SPK-Pad1)") (class "Default")
      (node (ref "L_SPK") (pin "1") (pinfunction "1_1") (pintype "passive"))
      (node (ref "U$4") (pin "L+") (pinfunction "L+_L+") (pintype "bidirectional"))
    )
    (net (code "62") (name "Net-(L_SPK-Pad2)") (class "Default")
      (node (ref "L_SPK") (pin "2") (pinfunction "2_2") (pintype "passive"))
      (node (ref "U$4") (pin "L-") (pinfunction "L-_L-") (pintype "bidirectional"))
    )
    (net (code "63") (name "Net-(R_SPK-Pad1)") (class "Default")
      (node (ref "R_SPK") (pin "1") (pinfunction "1_1") (pintype "passive"))
      (node (ref "U$4") (pin "R+") (pinfunction "R+_R+") (pintype "bidirectional"))
    )
    (net (code "64") (name "Net-(R_SPK-Pad2)") (class "Default")
      (node (ref "R_SPK") (pin "2") (pinfunction "2_2") (pintype "passive"))
      (node (ref "U$4") (pin "R-") (pinfunction "R-_R-") (pintype "bidirectional"))
    )
    (net (code "65") (name "Net-(U$1-27{slash}A16)") (class "Default")
      (node (ref "C4") (pin "2") (pinfunction "2_2") (pintype "passive"))
      (node (ref "R8") (pin "2") (pinfunction "2_2") (pintype "passive"))
      (node (ref "S4") (pin "3") (pinfunction "3_3") (pintype "passive"))
      (node (ref "S4") (pin "4") (pinfunction "4_4") (pintype "passive"))
      (node (ref "U$1") (pin "27") (pinfunction "27/A16_27") (pintype "bidirectional"))
    )
    (net (code "66") (name "Net-(U$1-28{slash}A17)") (class "Default")
      (node (ref "C3") (pin "2") (pinfunction "2_2") (pintype "passive"))
      (node (ref "R7") (pin "2") (pinfunction "2_2") (pintype "passive"))
      (node (ref "S3") (pin "3") (pinfunction "3_3") (pintype "passive"))
      (node (ref "S3") (pin "4") (pinfunction "4_4") (pintype "passive"))
      (node (ref "U$1") (pin "28") (pinfunction "28/A17_28") (pintype "bidirectional"))
    )
    (net (code "67") (name "unconnected-(J_BT_BOARD_1-Pad3.3)") (class "Default")
      (node (ref "J_BT_BOARD_1") (pin "3.3") (pinfunction "3.3_3.3") (pintype "bidirectional"))
    )
    (net (code "68") (name "unconnected-(MICRO_SD-NC-Pad1)") (class "Default")
      (node (ref "MICRO_SD") (pin "1") (pinfunction "NC_1") (pintype "bidirectional"))
    )
    (net (code "69") (name "unconnected-(MICRO_SD-RSV-Pad8)") (class "Default")
      (node (ref "MICRO_SD") (pin "8") (pinfunction "RSV_8") (pintype "bidirectional"))
    )
    (net (code "70") (name "unconnected-(U$1-PadPGM)") (class "Default")
      (node (ref "U$1") (pin "PGM") (pinfunction "PGM_PGM") (pintype "bidirectional"))
    )
  )
)
